# eos26_scan_cable_adapter.net
KiCad netlist of a schematic drawn in Altium Designer
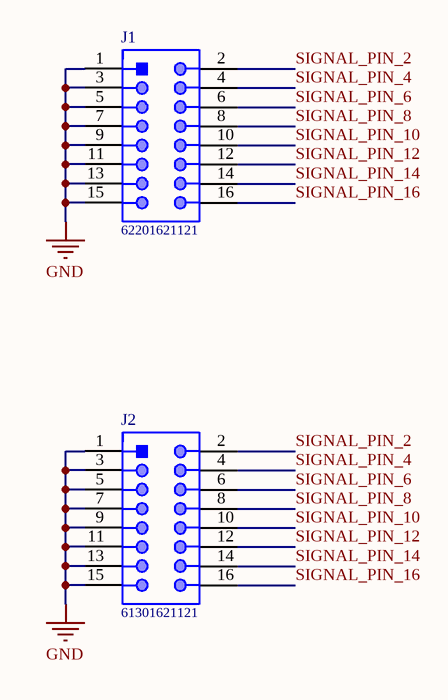
[diagram p0: eos26_scan_cable_adapter.SchDoc]

(export (version "E")
  (design (tool "Eeschema 10.0.6"))
  (components
    (comp (ref "J1")
      (value "62201621121")
      (footprint "62201621121")
      (description "THT Vertical Pin Header WR-PHD, Pitch 1.27 mm, Dual Row, 16 pins")
      (fields (field (name "MANUFACTURER") "Wurth Elektronik") (field (name "PUBLISHER") "WurthElektronik"))
      (libsource (lib "Altium Content Vault") (part "WE-CN-2P-M-R16"))
    )
    (comp (ref "J2")
      (value "61301621121")
      (footprint "61301621121")
      (description "THT Vertical Pin Header WR-PHD, Pitch 2.54 mm, Dual Row, 16 pins")
      (fields (field (name "MANUFACTURER") "Wurth Elektronik") (field (name "PUBLISHER") "WurthElektronik"))
      (libsource (lib "Altium Content Vault") (part "WE-CN-2P-M-R16"))
    )
  )
  (nets
    (net (code "1") (name "/SIGNAL_PIN_2") (class "Default")
      (node (ref "J1") (pin "2") (pinfunction "2_2") (pintype "passive"))
      (node (ref "J2") (pin "2") (pinfunction "2_2") (pintype "passive"))
    )
    (net (code "2") (name "/SIGNAL_PIN_4") (class "Default")
      (node (ref "J1") (pin "4") (pinfunction "4_4") (pintype "passive"))
      (node (ref "J2") (pin "4") (pinfunction "4_4") (pintype "passive"))
    )
    (net (code "3") (name "/SIGNAL_PIN_6") (class "Default")
      (node (ref "J1") (pin "6") (pinfunction "6_6") (pintype "passive"))
      (node (ref "J2") (pin "6") (pinfunction "6_6") (pintype "passive"))
    )
    (net (code "4") (name "/SIGNAL_PIN_8") (class "Default")
      (node (ref "J1") (pin "8") (pinfunction "8_8") (pintype "passive"))
      (node (ref "J2") (pin "8") (pinfunction "8_8") (pintype "passive"))
    )
    (net (code "5") (name "/SIGNAL_PIN_10") (class "Default")
      (node (ref "J1") (pin "10") (pinfunction "10_10") (pintype "passive"))
      (node (ref "J2") (pin "10") (pinfunction "10_10") (pintype "passive"))
    )
    (net (code "6") (name "/SIGNAL_PIN_12") (class "Default")
      (node (ref "J1") (pin "12") (pinfunction "12_12") (pintype "passive"))
      (node (ref "J2") (pin "12") (pinfunction "12_12") (pintype "passive"))
    )
    (net (code "7") (name "/SIGNAL_PIN_14") (class "Default")
      (node (ref "J1") (pin "14") (pinfunction "14_14") (pintype "passive"))
      (node (ref "J2") (pin "14") (pinfunction "14_14") (pintype "passive"))
    )
    (net (code "8") (name "/SIGNAL_PIN_16") (class "Default")
      (node (ref "J1") (pin "16") (pinfunction "16_16") (pintype "passive"))
      (node (ref "J2") (pin "16") (pinfunction "16_16") (pintype "passive"))
    )
    (net (code "9") (name "GND") (class "Default")
      (node (ref "J1") (pin "1") (pinfunction "1_1") (pintype "passive"))
      (node (ref "J1") (pin "11") (pinfunction "11_11") (pintype "passive"))
      (node (ref "J1") (pin "13") (pinfunction "13_13") (pintype "passive"))
      (node (ref "J1") (pin "15") (pinfunction "15_15") (pintype "passive"))
      (node (ref "J1") (pin "3") (pinfunction "3_3") (pintype "passive"))
      (node (ref "J1") (pin "5") (pinfunction "5_5") (pintype "passive"))
      (node (ref "J1") (pin "7") (pinfunction "7_7") (pintype "passive"))
      (node (ref "J1") (pin "9") (pinfunction "9_9") (pintype "passive"))
      (node (ref "J2") (pin "1") (pinfunction "1_1") (pintype "passive"))
      (node (ref "J2") (pin "11") (pinfunction "11_11") (pintype "passive"))
      (node (ref "J2") (pin "13") (pinfunction "13_13") (pintype "passive"))
      (node (ref "J2") (pin "15") (pinfunction "15_15") (pintype "passive"))
      (node (ref "J2") (pin "3") (pinfunction "3_3") (pintype "passive"))
      (node (ref "J2") (pin "5") (pinfunction "5_5") (pintype "passive"))
      (node (ref "J2") (pin "7") (pinfunction "7_7") (pintype "passive"))
      (node (ref "J2") (pin "9") (pinfunction "9_9") (pintype "passive"))
    )
  )
)
